# Diagrama-esquematico-oscilador-astavel.net
KiCad netlist of a schematic drawn in EAGLE
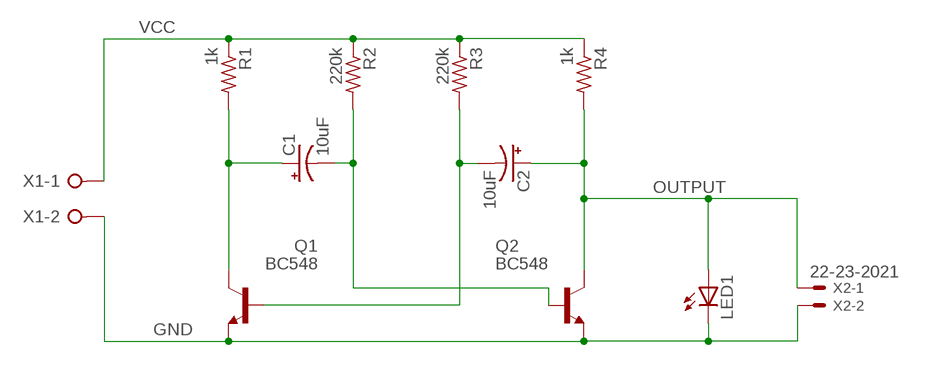
[diagram p0: schematic, sheet 1]

(export (version "E")
  (design (tool "Eeschema 10.0.6"))
  (components
    (comp (ref "C1")
      (value "10uF")
      (footprint "eagle-import:E2-4")
      (libsource (lib "eagle-import") (part "CPOL-USE2-4"))
    )
    (comp (ref "C2")
      (value "10uF")
      (footprint "eagle-import:E2-4")
      (libsource (lib "eagle-import") (part "CPOL-USE2-4"))
    )
    (comp (ref "LED1")
      (value "LED5MM")
      (footprint "eagle-import:LED5MM")
      (libsource (lib "eagle-import") (part "LED5MM"))
    )
    (comp (ref "Q1")
      (value "BC548")
      (footprint "eagle-import:TO92-EBC")
      (libsource (lib "eagle-import") (part "BC548"))
    )
    (comp (ref "Q2")
      (value "BC548")
      (footprint "eagle-import:TO92-EBC")
      (libsource (lib "eagle-import") (part "BC548"))
    )
    (comp (ref "R1")
      (value "1k")
      (footprint "eagle-import:0207_10")
      (libsource (lib "eagle-import") (part "R-US_0207/10"))
    )
    (comp (ref "R2")
      (value "220k")
      (footprint "eagle-import:0207_10")
      (libsource (lib "eagle-import") (part "R-US_0207/10"))
    )
    (comp (ref "R3")
      (value "220k")
      (footprint "eagle-import:0207_10")
      (libsource (lib "eagle-import") (part "R-US_0207/10"))
    )
    (comp (ref "R4")
      (value "1k")
      (footprint "eagle-import:0207_10")
      (libsource (lib "eagle-import") (part "R-US_0207/10"))
    )
    (comp (ref "X1")
      (value "W237-02P")
      (footprint "eagle-import:W237-132")
      (libsource (lib "eagle-import") (part "W237-02P"))
    )
    (comp (ref "X2")
      (value "22-23-2021")
      (footprint "eagle-import:22-23-2021")
      (fields (field (name "MF") "MOLEX"))
      (libsource (lib "eagle-import") (part "22-23-2021"))
    )
  )
  (nets
    (net (code "1") (name "/GND") (class "Default")
      (node (ref "LED1") (pin "K") (pinfunction "C_K") (pintype "passive"))
      (node (ref "Q1") (pin "E") (pinfunction "E_E") (pintype "passive"))
      (node (ref "Q2") (pin "E") (pinfunction "E_E") (pintype "passive"))
      (node (ref "X1") (pin "2") (pinfunction "KL_2") (pintype "passive"))
      (node (ref "X2") (pin "2") (pinfunction "S_2") (pintype "passive"))
    )
    (net (code "2") (name "/OUTPUT") (class "Default")
      (node (ref "C2") (pin "+") (pinfunction "+_+") (pintype "passive"))
      (node (ref "LED1") (pin "A") (pinfunction "A_A") (pintype "passive"))
      (node (ref "Q2") (pin "C") (pinfunction "C_C") (pintype "passive"))
      (node (ref "R4") (pin "2") (pinfunction "2_2") (pintype "passive"))
      (node (ref "X2") (pin "1") (pinfunction "S_1") (pintype "passive"))
    )
    (net (code "3") (name "/VCC") (class "Default")
      (node (ref "R1") (pin "1") (pinfunction "1_1") (pintype "passive"))
      (node (ref "R2") (pin "1") (pinfunction "1_1") (pintype "passive"))
      (node (ref "R3") (pin "1") (pinfunction "1_1") (pintype "passive"))
      (node (ref "R4") (pin "1") (pinfunction "1_1") (pintype "passive"))
      (node (ref "X1") (pin "1") (pinfunction "KL_1") (pintype "passive"))
    )
    (net (code "4") (name "Net-(C1-Pad+)") (class "Default")
      (node (ref "C1") (pin "+") (pinfunction "+_+") (pintype "passive"))
      (node (ref "Q1") (pin "C") (pinfunction "C_C") (pintype "passive"))
      (node (ref "R1") (pin "2") (pinfunction "2_2") (pintype "passive"))
    )
    (net (code "5") (name "Net-(C1-Pad-)") (class "Default")
      (node (ref "C1") (pin "-") (pinfunction "-_-") (pintype "passive"))
      (node (ref "Q2") (pin "B") (pinfunction "B_B") (pintype "passive"))
      (node (ref "R2") (pin "2") (pinfunction "2_2") (pintype "passive"))
    )
    (net (code "6") (name "Net-(C2-Pad-)") (class "Default")
      (node (ref "C2") (pin "-") (pinfunction "-_-") (pintype "passive"))
      (node (ref "Q1") (pin "B") (pinfunction "B_B") (pintype "passive"))
      (node (ref "R3") (pin "2") (pinfunction "2_2") (pintype "passive"))
    )
  )
)
